# CANOPi_Baseboard_RTC.net
KiCad netlist of a schematic drawn in Altium Designer
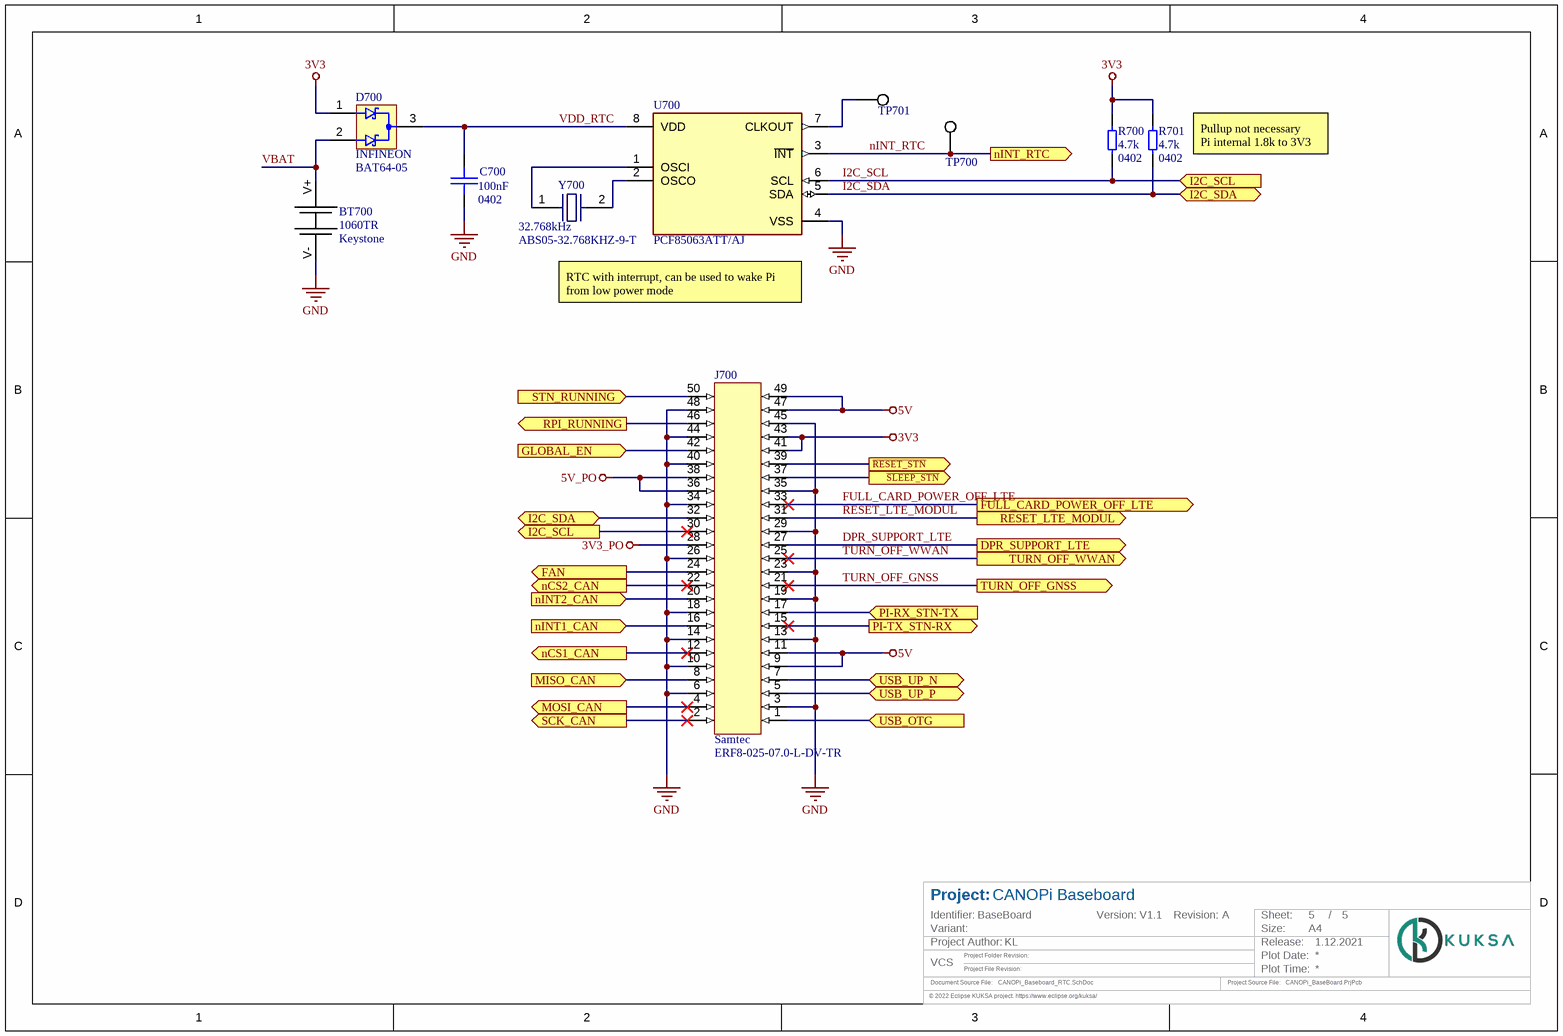
[diagram p0: CANOPi_Baseboard_RTC.SchDoc]

(export (version "E")
  (design (tool "Eeschema 10.0.6"))
  (components
    (comp (ref "BT700")
      (value "KEYSTONE - 1060")
      (footprint "KEYSTONE - 1060-Footprint-1")
      (description "Batterie Halter (offen) Kreisförmige Scheibe, 20,0mm 1 Zellen SMD (SMT) Tab")
      (fields (field (name "MANUFACTURER PART NUMBER") "1060TR") (field (name "MANUFACTURER") "Keystone"))
      (libsource (lib "ShareLib") (part "KEYSTONE - 1060"))
    )
    (comp (ref "C700")
      (value "CAP 0402 100n -10% +10% 6.3V X7R")
      (footprint "CAP 0402 [1005 Metric] X050 N")
      (description "SMD/SMT 0402 6.3V -10% +10% X7R - Multilayer Ceramic Capacitors MLCC")
      (fields
        (field (name "MANUFACTURER") "MURATA")
        (field (name "CAPACITANCE") "100nF")
        (field (name "MANUFACTURER PART NUMBER") "GRM155R70J104KA01#")
        (field (name "CASE") "0402")
      )
      (libsource (lib "ShareLib") (part "Capacitor non-polarized - Standard Schematic"))
    )
    (comp (ref "D700")
      (value "INFINEON - BAT64-05")
      (footprint "INFINEON - BAT64-04")
      (description "Dual Silicon Schottky Diodes")
      (fields (field (name "MANUFACTURER") "INFINEON") (field (name "MANUFACTURER PART NUMBER") "BAT64-05"))
      (libsource (lib "ShareLib") (part "Dual Schottky barrier rectifier"))
    )
    (comp (ref "J700")
      (value "SAMTEC - ERF8-025-07.0-L-DV-TR")
      (footprint "SAMTEC - ERF-025-05.0-L-DV-TR-Footprint-1")
      (description "50 Poliger Steckverbinder Sockel, äußere Abdeckungskontakte Oberflächenmontage Gold")
      (fields
        (field (name "MANUFACTURER") "Samtec")
        (field (name "MANUFACTURER PART NUMBER") "ERF8-025-07.0-L-DV-TR")
      )
      (libsource (lib "ShareLib") (part "SAMTEC - ERF8-025-07.0-L-DV-TR"))
    )
    (comp (ref "R700")
      (value "RES 0402 4K7 1% 0W0625")
      (footprint "RES 0402 [1005 Metric]_N")
      (description "RC0402 series chip resistor with lead-free terminations made by thick film process")
      (fields
        (field (name "RESISTANCE") "4.7k")
        (field (name "MANUFACTURER PART NUMBER") "RC0402FR-074K7L")
        (field (name "MANUFACTURER") "YAGEO")
        (field (name "CASE") "0402")
      )
      (libsource (lib "ShareLib") (part "Standard Schematic - Resistor Universal"))
    )
    (comp (ref "R701")
      (value "RES 0402 4K7 1% 0W0625")
      (footprint "RES 0402 [1005 Metric]_N")
      (description "RC0402 series chip resistor with lead-free terminations made by thick film process")
      (fields
        (field (name "RESISTANCE") "4.7k")
        (field (name "MANUFACTURER PART NUMBER") "RC0402FR-074K7L")
        (field (name "MANUFACTURER") "YAGEO")
        (field (name "CASE") "0402")
      )
      (libsource (lib "ShareLib") (part "Standard Schematic - Resistor Universal"))
    )
    (comp (ref "TP700")
      (value "Testpad, 0.8mm x 0.8mm, round")
      (footprint "Testpad, 0.8mm x 0.8mm, round")
      (libsource (lib "ShareLib") (part "Testpoint (No BOM)"))
    )
    (comp (ref "TP701")
      (value "Testpad, 0.8mm x 0.8mm, round")
      (footprint "Testpad, 0.8mm x 0.8mm, round")
      (libsource (lib "ShareLib") (part "Testpoint (No BOM)"))
    )
    (comp (ref "U700")
      (value "PCF85063ATT/AJ")
      (footprint "FP-SOT505-1-MFG")
      (description "IC RTC CLK/CALENDAR I2C 8TSSOP")
      (fields
        (field (name "OCTOPART") "https://octopart.com/pcf85063att%2Faj-nxp+semiconductors-46729225")
        (field (name "MANUFACTURER") "NXP Semiconductors")
      )
      (libsource (lib "Altium Content Vault") (part "824269ce6ab1022c00e763b986ab016"))
    )
    (comp (ref "Y700")
      (value "ABRACON - ABS05-32.768KHZ-9-T")
      (footprint "ABRACON - ABS05-32.768KHZ-9-T")
      (description "Crystals 32.768KHz 9.0pF 20ppm -40C +85C")
      (fields
        (field (name "MANUFACTURER") "ABRACON")
        (field (name "MANUFACTURER PART NUMBER") "ABS05-32.768KHZ-9-T")
        (field (name "FREQUENCY") "32.768kHz")
      )
      (libsource (lib "ShareLib") (part "Component_1"))
    )
  )
  (nets
    (net (code "1") (name "/DPR_SUPPORT_LTE") (class "Default")
      (node (ref "J700") (pin "27") (pintype "input"))
    )
    (net (code "2") (name "/FAN") (class "Default") (node (ref "J700") (pin "24") (pintype "input")))
    (net (code "3") (name "/FULL_CARD_POWER_OFF_LTE") (class "Default")
      (node (ref "J700") (pin "33") (pintype "input+no_connect"))
    )
    (net (code "4") (name "/GLOBAL_EN") (class "Default") (node (ref "J700") (pin "42") (pintype "input")))
    (net (code "5") (name "/I2C_SCL") (class "Default")
      (node (ref "J700") (pin "30") (pintype "input"))
      (node (ref "R700") (pin "1") (pinfunction "1_1") (pintype "passive"))
      (node (ref "U700") (pin "6") (pinfunction "SCL_6") (pintype "input"))
    )
    (net (code "6") (name "/I2C_SDA") (class "Default")
      (node (ref "J700") (pin "32") (pintype "input"))
      (node (ref "R701") (pin "1") (pinfunction "1_1") (pintype "passive"))
      (node (ref "U700") (pin "5") (pinfunction "SDA_5") (pintype "bidirectional"))
    )
    (net (code "7") (name "/MISO_CAN") (class "Default") (node (ref "J700") (pin "8") (pintype "input")))
    (net (code "8") (name "/MOSI_CAN") (class "Default")
      (node (ref "J700") (pin "4") (pintype "input+no_connect"))
    )
    (net (code "9") (name "/PI-RX_STN-TX") (class "Default") (node (ref "J700") (pin "17") (pintype "input")))
    (net (code "10") (name "/PI-TX_STN-RX") (class "Default")
      (node (ref "J700") (pin "15") (pintype "input+no_connect"))
    )
    (net (code "11") (name "/RESET_LTE_MODUL") (class "Default")
      (node (ref "J700") (pin "31") (pintype "input"))
    )
    (net (code "12") (name "/RESET_STN") (class "Default") (node (ref "J700") (pin "39") (pintype "input")))
    (net (code "13") (name "/RPI_RUNNING") (class "Default") (node (ref "J700") (pin "46") (pintype "input")))
    (net (code "14") (name "/SCK_CAN") (class "Default")
      (node (ref "J700") (pin "2") (pintype "input+no_connect"))
    )
    (net (code "15") (name "/SLEEP_STN") (class "Default") (node (ref "J700") (pin "37") (pintype "input")))
    (net (code "16") (name "/STN_RUNNING") (class "Default") (node (ref "J700") (pin "50") (pintype "input")))
    (net (code "17") (name "/TURN_OFF_GNSS") (class "Default")
      (node (ref "J700") (pin "21") (pintype "input+no_connect"))
    )
    (net (code "18") (name "/TURN_OFF_WWAN") (class "Default")
      (node (ref "J700") (pin "25") (pintype "input+no_connect"))
    )
    (net (code "19") (name "/USB_OTG") (class "Default") (node (ref "J700") (pin "1") (pintype "input")))
    (net (code "20") (name "/USB_UP_N") (class "Default") (node (ref "J700") (pin "7") (pintype "input")))
    (net (code "21") (name "/USB_UP_P") (class "Default") (node (ref "J700") (pin "5") (pintype "input")))
    (net (code "22") (name "/VBAT") (class "Default")
      (node (ref "BT700") (pin "V+") (pintype "power_in"))
      (node (ref "D700") (pin "2") (pinfunction "2_2") (pintype "passive"))
    )
    (net (code "23") (name "/VDD_RTC") (class "Default")
      (node (ref "C700") (pin "2") (pinfunction "2_2") (pintype "passive"))
      (node (ref "D700") (pin "3") (pinfunction "3_3") (pintype "passive"))
      (node (ref "U700") (pin "8") (pinfunction "VDD_8") (pintype "power_in"))
    )
    (net (code "24") (name "/nCS1_CAN") (class "Default")
      (node (ref "J700") (pin "12") (pintype "input+no_connect"))
    )
    (net (code "25") (name "/nCS2_CAN") (class "Default")
      (node (ref "J700") (pin "22") (pintype "input+no_connect"))
    )
    (net (code "26") (name "/nINT1_CAN") (class "Default") (node (ref "J700") (pin "16") (pintype "input")))
    (net (code "27") (name "/nINT2_CAN") (class "Default") (node (ref "J700") (pin "20") (pintype "input")))
    (net (code "28") (name "/nINT_RTC") (class "Default")
      (node (ref "TP700") (pin "1") (pinfunction "1_1") (pintype "passive"))
      (node (ref "U700") (pin "3") (pinfunction "~{INT}_3") (pintype "output"))
    )
    (net (code "29") (name "3V3") (class "Default")
      (node (ref "D700") (pin "1") (pinfunction "1_1") (pintype "passive"))
      (node (ref "J700") (pin "41") (pintype "input"))
      (node (ref "J700") (pin "43") (pintype "input"))
      (node (ref "R700") (pin "2") (pinfunction "2_2") (pintype "passive"))
      (node (ref "R701") (pin "2") (pinfunction "2_2") (pintype "passive"))
    )
    (net (code "30") (name "3V3_PO") (class "Default") (node (ref "J700") (pin "28") (pintype "input")))
    (net (code "31") (name "5V") (class "Default")
      (node (ref "J700") (pin "11") (pintype "input"))
      (node (ref "J700") (pin "47") (pintype "input"))
      (node (ref "J700") (pin "49") (pintype "input"))
      (node (ref "J700") (pin "9") (pintype "input"))
    )
    (net (code "32") (name "5V_PO") (class "Default")
      (node (ref "J700") (pin "36") (pintype "input"))
      (node (ref "J700") (pin "38") (pintype "input"))
    )
    (net (code "33") (name "GND") (class "Default")
      (node (ref "BT700") (pin "V-") (pintype "power_in"))
      (node (ref "C700") (pin "1") (pinfunction "1_1") (pintype "passive"))
      (node (ref "J700") (pin "10") (pintype "input"))
      (node (ref "J700") (pin "13") (pintype "input"))
      (node (ref "J700") (pin "14") (pintype "input"))
      (node (ref "J700") (pin "18") (pintype "input"))
      (node (ref "J700") (pin "19") (pintype "input"))
      (node (ref "J700") (pin "23") (pintype "input"))
      (node (ref "J700") (pin "26") (pintype "input"))
      (node (ref "J700") (pin "29") (pintype "input"))
      (node (ref "J700") (pin "3") (pintype "input"))
      (node (ref "J700") (pin "34") (pintype "input"))
      (node (ref "J700") (pin "35") (pintype "input"))
      (node (ref "J700") (pin "40") (pintype "input"))
      (node (ref "J700") (pin "44") (pintype "input"))
      (node (ref "J700") (pin "45") (pintype "input"))
      (node (ref "J700") (pin "48") (pintype "input"))
      (node (ref "J700") (pin "6") (pintype "input"))
      (node (ref "U700") (pin "4") (pinfunction "VSS_4") (pintype "power_in"))
    )
    (net (code "34") (name "Net-(U700-CLKOUT)") (class "Default")
      (node (ref "TP701") (pin "1") (pinfunction "1_1") (pintype "passive"))
      (node (ref "U700") (pin "7") (pinfunction "CLKOUT_7") (pintype "output"))
    )
    (net (code "35") (name "Net-(U700-OSCI)") (class "Default")
      (node (ref "U700") (pin "1") (pinfunction "OSCI_1") (pintype "passive"))
      (node (ref "Y700") (pin "1") (pinfunction "1_1") (pintype "passive"))
    )
    (net (code "36") (name "Net-(U700-OSCO)") (class "Default")
      (node (ref "U700") (pin "2") (pinfunction "OSCO_2") (pintype "passive"))
      (node (ref "Y700") (pin "2") (pinfunction "2_2") (pintype "passive"))
    )
  )
)
